# 04_SQ3_SQ11.net
KiCad netlist of a schematic drawn in Altium Designer
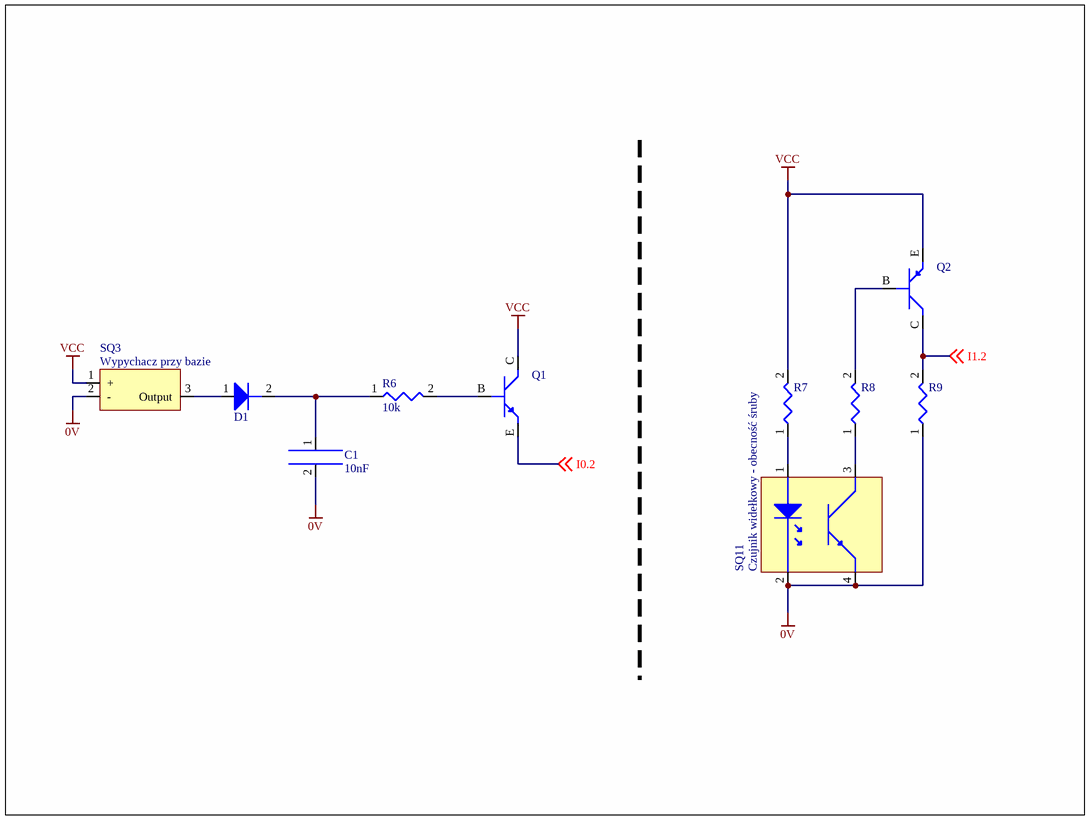
[diagram p0: [04] SQ3, SQ11.SchDoc]

(export (version "E")
  (design (tool "Eeschema 10.0.6"))
  (components
    (comp (ref "C1") (value "10nF") (libsource (lib "Schlib2") (part "Condensator")))
    (comp (ref "D1") (value "Dioda prostownicza") (libsource (lib "Schlib2") (part "Diode")))
    (comp (ref "Q1") (value "Transistor NPN") (libsource (lib "Schlib2") (part "Transistor NPN")))
    (comp (ref "Q2") (value "PNP Transistor") (libsource (lib "Schlib2") (part "PNP Transistor")))
    (comp (ref "R6") (value "10k") (libsource (lib "Schlib2") (part "Resistor")))
    (comp (ref "R7") (value "?R?") (libsource (lib "Schlib2") (part "Resistor")))
    (comp (ref "R8") (value "?R?") (libsource (lib "Schlib2") (part "Resistor")))
    (comp (ref "R9") (value "?R?") (libsource (lib "Schlib2") (part "Resistor")))
    (comp (ref "SQ3") (value "Wypychacz przy bazie") (libsource (lib "Schlib2") (part "Magnetic sensor PNP")))
    (comp (ref "SQ11")
      (value "Czujnik widełkowy - obecność śruby")
      (libsource (lib "Schlib1") (part "Czujnik widełkowy"))
    )
  )
  (nets
    (net (code "1") (name "0V") (class "Default")
      (node (ref "C1") (pin "2") (pinfunction "2_2") (pintype "passive"))
      (node (ref "R9") (pin "1") (pinfunction "3_1") (pintype "passive"))
      (node (ref "SQ11") (pin "2") (pinfunction "-_2") (pintype "passive"))
      (node (ref "SQ11") (pin "4") (pinfunction "5_4") (pintype "passive"))
      (node (ref "SQ3") (pin "2") (pinfunction "-_2") (pintype "passive"))
    )
    (net (code "2") (name "I0.2") (class "Default")
      (node (ref "Q1") (pin "E") (pinfunction "E_E") (pintype "passive"))
    )
    (net (code "3") (name "I1.2") (class "Default")
      (node (ref "Q2") (pin "C") (pinfunction "C_C") (pintype "passive"))
      (node (ref "R9") (pin "2") (pinfunction "4_2") (pintype "passive"))
    )
    (net (code "4") (name "Net-(D1-+)") (class "Default")
      (node (ref "D1") (pin "1") (pinfunction "+_1") (pintype "passive"))
      (node (ref "SQ3") (pin "3") (pinfunction "Output_3") (pintype "passive"))
    )
    (net (code "5") (name "Net-(D1--)") (class "Default")
      (node (ref "C1") (pin "1") (pinfunction "1_1") (pintype "passive"))
      (node (ref "D1") (pin "2") (pinfunction "-_2") (pintype "passive"))
      (node (ref "R6") (pin "1") (pinfunction "3_1") (pintype "passive"))
    )
    (net (code "6") (name "Net-(R6-4)") (class "Default")
      (node (ref "Q1") (pin "B") (pinfunction "B_B") (pintype "passive"))
      (node (ref "R6") (pin "2") (pinfunction "4_2") (pintype "passive"))
    )
    (net (code "7") (name "Net-(R7-3)") (class "Default")
      (node (ref "R7") (pin "1") (pinfunction "3_1") (pintype "passive"))
      (node (ref "SQ11") (pin "1") (pinfunction "+_1") (pintype "passive"))
    )
    (net (code "8") (name "Net-(R8-3)") (class "Default")
      (node (ref "R8") (pin "1") (pinfunction "3_1") (pintype "passive"))
      (node (ref "SQ11") (pin "3") (pinfunction "4_3") (pintype "passive"))
    )
    (net (code "9") (name "Net-(R8-4)") (class "Default")
      (node (ref "Q2") (pin "B") (pinfunction "B_B") (pintype "passive"))
      (node (ref "R8") (pin "2") (pinfunction "4_2") (pintype "passive"))
    )
    (net (code "10") (name "VCC") (class "Default")
      (node (ref "Q1") (pin "C") (pinfunction "C_C") (pintype "passive"))
      (node (ref "Q2") (pin "E") (pinfunction "E_E") (pintype "passive"))
      (node (ref "R7") (pin "2") (pinfunction "4_2") (pintype "passive"))
      (node (ref "SQ3") (pin "1") (pinfunction "+_1") (pintype "passive"))
    )
  )
)
